# r8_3_1284.net
KiCad netlist of a schematic drawn in EAGLE
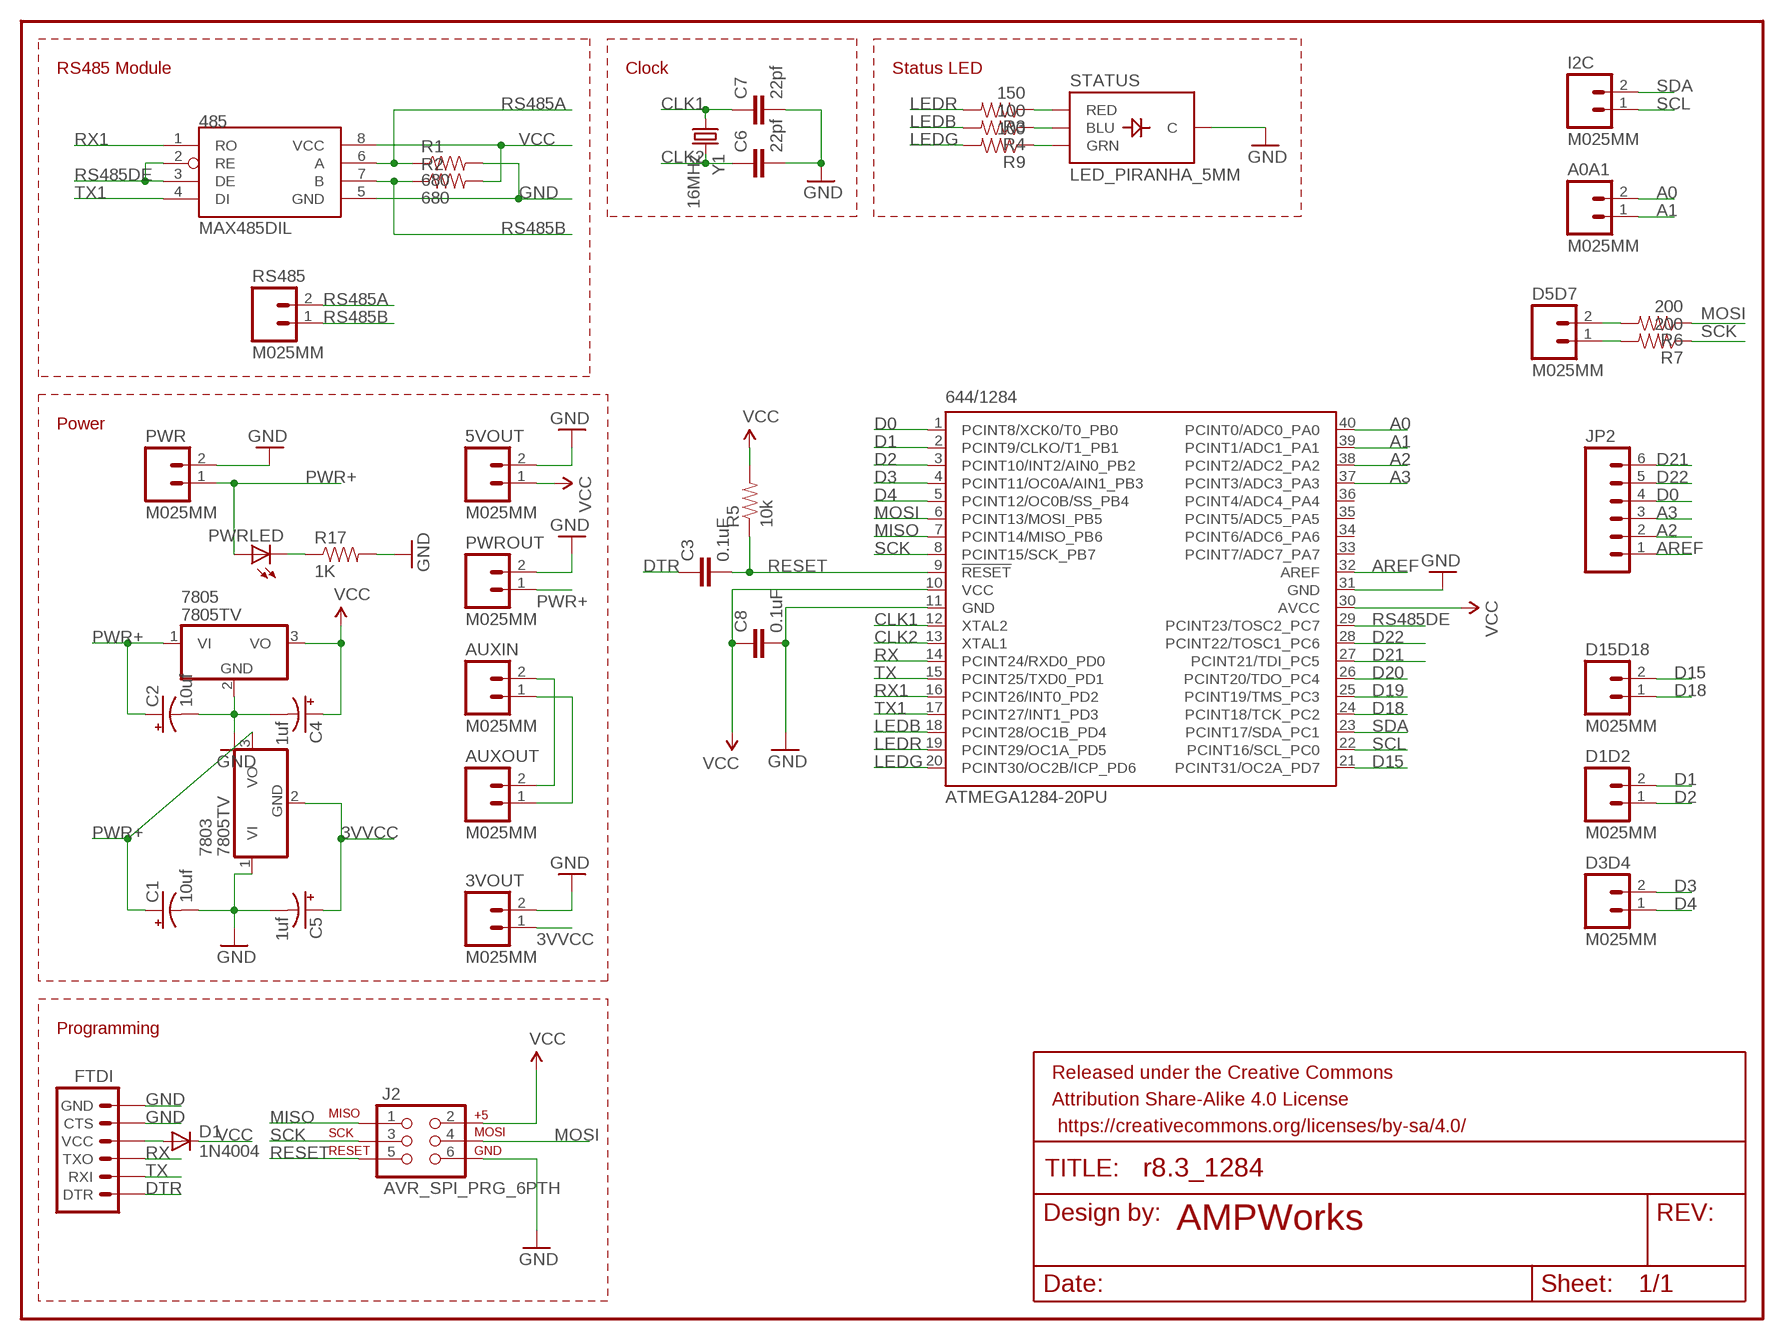
[diagram p0: schematic, sheet 1]

(export (version "E")
  (design (tool "Eeschema 10.0.6"))
  (components
    (comp (ref "3VOUT")
      (value "M025MM")
      (footprint "eagle-import:SCREWTERMINAL-5MM-2")
      (libsource (lib "eagle-import") (part "M025MM"))
    )
    (comp (ref "5VOUT")
      (value "M025MM")
      (footprint "eagle-import:SCREWTERMINAL-5MM-2")
      (libsource (lib "eagle-import") (part "M025MM"))
    )
    (comp (ref "485")
      (value "MAX485DIL")
      (footprint "eagle-import:DIL08")
      (libsource (lib "eagle-import") (part "MAX485DIL"))
    )
    (comp (ref "644/1284")
      (value "ATMEGA1284-20PU")
      (footprint "eagle-import:DIL40")
      (fields (field (name "MPN") "ATMEGA644-20PU"))
      (libsource (lib "eagle-import") (part "ATMEGA644-PU20"))
    )
    (comp (ref "7803")
      (value "7805TV")
      (footprint "eagle-import:TO220V")
      (libsource (lib "eagle-import") (part "78TV05"))
    )
    (comp (ref "7805")
      (value "7805TV")
      (footprint "eagle-import:TO220V")
      (libsource (lib "eagle-import") (part "78TV05"))
    )
    (comp (ref "A0A1")
      (value "M025MM")
      (footprint "eagle-import:SCREWTERMINAL-5MM-2")
      (libsource (lib "eagle-import") (part "M025MM"))
    )
    (comp (ref "AUXIN")
      (value "M025MM")
      (footprint "eagle-import:SCREWTERMINAL-5MM-2")
      (libsource (lib "eagle-import") (part "M025MM"))
    )
    (comp (ref "AUXOUT")
      (value "M025MM")
      (footprint "eagle-import:SCREWTERMINAL-5MM-2")
      (libsource (lib "eagle-import") (part "M025MM"))
    )
    (comp (ref "C1")
      (value "10uf")
      (footprint "eagle-import:CPOL-RADIAL-10UF-25V")
      (libsource (lib "eagle-import") (part "CAP_POLPTH2"))
    )
    (comp (ref "C2")
      (value "10uf")
      (footprint "eagle-import:CPOL-RADIAL-10UF-25V")
      (libsource (lib "eagle-import") (part "CAP_POLPTH2"))
    )
    (comp (ref "C3")
      (value "0.1uF")
      (footprint "eagle-import:CAP-PTH-SMALL")
      (libsource (lib "eagle-import") (part "CAPPTH"))
    )
    (comp (ref "C4")
      (value "1uf")
      (footprint "eagle-import:CPOL-RADIAL-10UF-25V")
      (libsource (lib "eagle-import") (part "CAP_POLPTH2"))
    )
    (comp (ref "C5")
      (value "1uf")
      (footprint "eagle-import:CPOL-RADIAL-10UF-25V")
      (libsource (lib "eagle-import") (part "CAP_POLPTH2"))
    )
    (comp (ref "C6")
      (value "22pf")
      (footprint "eagle-import:CAP-PTH-SMALL")
      (libsource (lib "eagle-import") (part "CAPPTH"))
    )
    (comp (ref "C7")
      (value "22pf")
      (footprint "eagle-import:CAP-PTH-SMALL")
      (libsource (lib "eagle-import") (part "CAPPTH"))
    )
    (comp (ref "C8")
      (value "0.1uF")
      (footprint "eagle-import:CAP-PTH-SMALL")
      (libsource (lib "eagle-import") (part "CAPPTH"))
    )
    (comp (ref "D1")
      (value "1N4004")
      (footprint "eagle-import:DO41-10")
      (libsource (lib "eagle-import") (part "1N4004"))
    )
    (comp (ref "D1D2")
      (value "M025MM")
      (footprint "eagle-import:SCREWTERMINAL-5MM-2")
      (libsource (lib "eagle-import") (part "M025MM"))
    )
    (comp (ref "D3D4")
      (value "M025MM")
      (footprint "eagle-import:SCREWTERMINAL-5MM-2")
      (libsource (lib "eagle-import") (part "M025MM"))
    )
    (comp (ref "D5D7")
      (value "M025MM")
      (footprint "eagle-import:SCREWTERMINAL-5MM-2")
      (libsource (lib "eagle-import") (part "M025MM"))
    )
    (comp (ref "D15D18")
      (value "M025MM")
      (footprint "eagle-import:SCREWTERMINAL-5MM-2")
      (libsource (lib "eagle-import") (part "M025MM"))
    )
    (comp (ref "FRAME1")
      (value "FRAME-LETTER")
      (footprint "eagle-import:CREATIVE_COMMONS")
      (libsource (lib "eagle-import") (part "FRAME-LETTER"))
    )
    (comp (ref "FTDI")
      (value "ARDUINO_SERIAL_PROGRAMPTH")
      (footprint "eagle-import:1X06")
      (libsource (lib "eagle-import") (part "ARDUINO_SERIAL_PROGRAMPTH"))
    )
    (comp (ref "I2C")
      (value "M025MM")
      (footprint "eagle-import:SCREWTERMINAL-5MM-2")
      (libsource (lib "eagle-import") (part "M025MM"))
    )
    (comp (ref "J2")
      (value "AVR_SPI_PRG_6PTH")
      (footprint "eagle-import:2X3")
      (libsource (lib "eagle-import") (part "AVR_SPI_PRG_6PTH"))
    )
    (comp (ref "JP2")
      (value "M06NO_SILK")
      (footprint "eagle-import:1X06_NO_SILK")
      (libsource (lib "eagle-import") (part "M06NO_SILK"))
    )
    (comp (ref "PWR")
      (value "M025MM")
      (footprint "eagle-import:SCREWTERMINAL-5MM-2")
      (libsource (lib "eagle-import") (part "M025MM"))
    )
    (comp (ref "PWRLED")
      (value "LED5MM")
      (footprint "eagle-import:LED5MM")
      (libsource (lib "eagle-import") (part "LED5MM"))
    )
    (comp (ref "PWROUT")
      (value "M025MM")
      (footprint "eagle-import:SCREWTERMINAL-5MM-2")
      (libsource (lib "eagle-import") (part "M025MM"))
    )
    (comp (ref "R1")
      (value "680")
      (footprint "eagle-import:AXIAL-0.4")
      (libsource (lib "eagle-import") (part "SparkFun-Resistors_RESISTORPTH-1/4W"))
    )
    (comp (ref "R2")
      (value "680")
      (footprint "eagle-import:AXIAL-0.4")
      (libsource (lib "eagle-import") (part "SparkFun-Resistors_RESISTORPTH-1/4W"))
    )
    (comp (ref "R3")
      (value "150")
      (footprint "eagle-import:AXIAL-0.4")
      (libsource (lib "eagle-import") (part "RESISTORPTH-1/4W"))
    )
    (comp (ref "R4")
      (value "100")
      (footprint "eagle-import:AXIAL-0.4")
      (libsource (lib "eagle-import") (part "RESISTORPTH-1/4W"))
    )
    (comp (ref "R5")
      (value "10k")
      (footprint "eagle-import:AXIAL-0.4")
      (libsource (lib "eagle-import") (part "RESISTORPTH-1/4W"))
    )
    (comp (ref "R6")
      (value "200")
      (footprint "eagle-import:AXIAL-0.4")
      (libsource (lib "eagle-import") (part "RESISTORPTH-1/4W"))
    )
    (comp (ref "R7")
      (value "200")
      (footprint "eagle-import:AXIAL-0.4")
      (libsource (lib "eagle-import") (part "RESISTORPTH-1/4W"))
    )
    (comp (ref "R9")
      (value "100")
      (footprint "eagle-import:AXIAL-0.4")
      (libsource (lib "eagle-import") (part "RESISTORPTH-1/4W"))
    )
    (comp (ref "R17")
      (value "1K")
      (footprint "eagle-import:AXIAL-0.4")
      (libsource (lib "eagle-import") (part "SparkFun-Resistors_RESISTORPTH-1/4W"))
    )
    (comp (ref "RS485")
      (value "M025MM")
      (footprint "eagle-import:SCREWTERMINAL-5MM-2")
      (libsource (lib "eagle-import") (part "M025MM"))
    )
    (comp (ref "STATUS")
      (value "LED_PIRANHA_5MM")
      (footprint "eagle-import:LED_PIRANHA_5MM")
      (libsource (lib "eagle-import") (part "LED_PIRANHA_5MM"))
    )
    (comp (ref "Y1")
      (value "16MHz")
      (footprint "eagle-import:HC49US")
      (libsource (lib "eagle-import") (part "CRYSTALHC49US"))
    )
  )
  (nets
    (net (code "1") (name "/3VVCC") (class "Default")
      (node (ref "3VOUT") (pin "1") (pinfunction "1_1") (pintype "passive"))
      (node (ref "7803") (pin "2") (pinfunction "GND_2") (pintype "passive"))
      (node (ref "C5") (pin "1") (pinfunction "+_1") (pintype "passive"))
    )
    (net (code "2") (name "/A0") (class "Default")
      (node (ref "644/1284") (pin "40") (pinfunction "PCINT0/ADC0_PA0_40") (pintype "bidirectional"))
      (node (ref "A0A1") (pin "2") (pinfunction "2_2") (pintype "passive"))
    )
    (net (code "3") (name "/A1") (class "Default")
      (node (ref "644/1284") (pin "39") (pinfunction "PCINT1/ADC1_PA1_39") (pintype "bidirectional"))
      (node (ref "A0A1") (pin "1") (pinfunction "1_1") (pintype "passive"))
    )
    (net (code "4") (name "/A2") (class "Default")
      (node (ref "644/1284") (pin "38") (pinfunction "PCINT2/ADC2_PA2_38") (pintype "bidirectional"))
      (node (ref "JP2") (pin "2") (pinfunction "2_2") (pintype "passive"))
    )
    (net (code "5") (name "/A3") (class "Default")
      (node (ref "644/1284") (pin "37") (pinfunction "PCINT3/ADC3_PA3_37") (pintype "bidirectional"))
      (node (ref "JP2") (pin "3") (pinfunction "3_3") (pintype "passive"))
    )
    (net (code "6") (name "/AREF") (class "Default")
      (node (ref "644/1284") (pin "32") (pinfunction "AREF_32") (pintype "passive"))
      (node (ref "JP2") (pin "1") (pinfunction "1_1") (pintype "passive"))
    )
    (net (code "7") (name "/CLK1") (class "Default")
      (node (ref "644/1284") (pin "12") (pinfunction "XTAL2_12") (pintype "output"))
      (node (ref "C7") (pin "1") (pinfunction "1_1") (pintype "passive"))
      (node (ref "Y1") (pin "1") (pinfunction "1_1") (pintype "passive"))
    )
    (net (code "8") (name "/CLK2") (class "Default")
      (node (ref "644/1284") (pin "13") (pinfunction "XTAL1_13") (pintype "input"))
      (node (ref "C6") (pin "1") (pinfunction "1_1") (pintype "passive"))
      (node (ref "Y1") (pin "2") (pinfunction "2_2") (pintype "passive"))
    )
    (net (code "9") (name "/D0") (class "Default")
      (node (ref "644/1284") (pin "1") (pinfunction "PCINT8/XCK0/T0_PB0_1") (pintype "bidirectional"))
      (node (ref "JP2") (pin "4") (pinfunction "4_4") (pintype "passive"))
    )
    (net (code "10") (name "/D1") (class "Default")
      (node (ref "644/1284") (pin "2") (pinfunction "PCINT9/CLKO/T1_PB1_2") (pintype "bidirectional"))
      (node (ref "D1D2") (pin "2") (pinfunction "2_2") (pintype "passive"))
    )
    (net (code "11") (name "/D2") (class "Default")
      (node (ref "644/1284") (pin "3") (pinfunction "PCINT10/INT2/AIN0_PB2_3") (pintype "bidirectional"))
      (node (ref "D1D2") (pin "1") (pinfunction "1_1") (pintype "passive"))
    )
    (net (code "12") (name "/D3") (class "Default")
      (node (ref "644/1284") (pin "4") (pinfunction "PCINT11/OC0A/AIN1_PB3_4") (pintype "bidirectional"))
      (node (ref "D3D4") (pin "2") (pinfunction "2_2") (pintype "passive"))
    )
    (net (code "13") (name "/D4") (class "Default")
      (node (ref "644/1284") (pin "5") (pinfunction "PCINT12/OC0B/SS_PB4_5") (pintype "bidirectional"))
      (node (ref "D3D4") (pin "1") (pinfunction "1_1") (pintype "passive"))
    )
    (net (code "14") (name "/D15") (class "Default")
      (node (ref "644/1284") (pin "21") (pinfunction "PCINT31/OC2A_PD7_21") (pintype "bidirectional"))
      (node (ref "D15D18") (pin "2") (pinfunction "2_2") (pintype "passive"))
    )
    (net (code "15") (name "/D18") (class "Default")
      (node (ref "644/1284") (pin "24") (pinfunction "PCINT18/TCK_PC2_24") (pintype "bidirectional"))
      (node (ref "D15D18") (pin "1") (pinfunction "1_1") (pintype "passive"))
    )
    (net (code "16") (name "/D19") (class "Default")
      (node (ref "644/1284") (pin "25") (pinfunction "PCINT19/TMS_PC3_25") (pintype "bidirectional"))
    )
    (net (code "17") (name "/D20") (class "Default")
      (node (ref "644/1284") (pin "26") (pinfunction "PCINT20/TDO_PC4_26") (pintype "bidirectional"))
    )
    (net (code "18") (name "/D21") (class "Default")
      (node (ref "644/1284") (pin "27") (pinfunction "PCINT21/TDI_PC5_27") (pintype "bidirectional"))
      (node (ref "JP2") (pin "6") (pinfunction "6_6") (pintype "passive"))
    )
    (net (code "19") (name "/D22") (class "Default")
      (node (ref "644/1284") (pin "28") (pinfunction "PCINT22/TOSC1_PC6_28") (pintype "bidirectional"))
      (node (ref "JP2") (pin "5") (pinfunction "5_5") (pintype "passive"))
    )
    (net (code "20") (name "/DTR") (class "Default")
      (node (ref "C3") (pin "1") (pinfunction "1_1") (pintype "passive"))
      (node (ref "FTDI") (pin "DTR") (pinfunction "DTR_DTR") (pintype "passive"))
    )
    (net (code "21") (name "/LEDB") (class "Default")
      (node (ref "644/1284") (pin "18") (pinfunction "PCINT28/OC1B_PD4_18") (pintype "bidirectional"))
      (node (ref "R4") (pin "P$2") (pinfunction "2_P$2") (pintype "passive"))
    )
    (net (code "22") (name "/LEDG") (class "Default")
      (node (ref "644/1284") (pin "20") (pinfunction "PCINT30/OC2B/ICP_PD6_20") (pintype "bidirectional"))
      (node (ref "R9") (pin "P$2") (pinfunction "2_P$2") (pintype "passive"))
    )
    (net (code "23") (name "/LEDR") (class "Default")
      (node (ref "644/1284") (pin "19") (pinfunction "PCINT29/OC1A_PD5_19") (pintype "bidirectional"))
      (node (ref "R3") (pin "P$2") (pinfunction "2_P$2") (pintype "passive"))
    )
    (net (code "24") (name "/MISO") (class "Default")
      (node (ref "644/1284") (pin "7") (pinfunction "PCINT14/MISO_PB6_7") (pintype "bidirectional"))
      (node (ref "J2") (pin "1") (pinfunction "1_1") (pintype "passive"))
    )
    (net (code "25") (name "/MOSI") (class "Default")
      (node (ref "644/1284") (pin "6") (pinfunction "PCINT13/MOSI_PB5_6") (pintype "bidirectional"))
      (node (ref "J2") (pin "4") (pinfunction "4_4") (pintype "passive"))
      (node (ref "R6") (pin "P$1") (pinfunction "1_P$1") (pintype "passive"))
    )
    (net (code "26") (name "/PWR+") (class "Default")
      (node (ref "7803") (pin "3") (pinfunction "VO_3") (pintype "passive"))
      (node (ref "7805") (pin "1") (pinfunction "VI_1") (pintype "input"))
      (node (ref "C1") (pin "1") (pinfunction "+_1") (pintype "passive"))
      (node (ref "C2") (pin "1") (pinfunction "+_1") (pintype "passive"))
      (node (ref "PWR") (pin "1") (pinfunction "1_1") (pintype "passive"))
      (node (ref "PWRLED") (pin "A") (pinfunction "A_A") (pintype "passive"))
      (node (ref "PWROUT") (pin "1") (pinfunction "1_1") (pintype "passive"))
    )
    (net (code "27") (name "/RESET") (class "Default")
      (node (ref "644/1284") (pin "9") (pinfunction "~{RESET}_9") (pintype "input"))
      (node (ref "C3") (pin "2") (pinfunction "2_2") (pintype "passive"))
      (node (ref "J2") (pin "5") (pinfunction "5_5") (pintype "passive"))
      (node (ref "R5") (pin "P$1") (pinfunction "1_P$1") (pintype "passive"))
    )
    (net (code "28") (name "/RS485A") (class "Default")
      (node (ref "485") (pin "6") (pinfunction "A_6") (pintype "bidirectional"))
      (node (ref "R1") (pin "P$1") (pinfunction "1_P$1") (pintype "passive"))
      (node (ref "RS485") (pin "2") (pinfunction "2_2") (pintype "passive"))
    )
    (net (code "29") (name "/RS485B") (class "Default")
      (node (ref "485") (pin "7") (pinfunction "B_7") (pintype "bidirectional"))
      (node (ref "R2") (pin "P$1") (pinfunction "1_P$1") (pintype "passive"))
      (node (ref "RS485") (pin "1") (pinfunction "1_1") (pintype "passive"))
    )
    (net (code "30") (name "/RS485DE") (class "Default")
      (node (ref "485") (pin "2") (pinfunction "RE_2") (pintype "bidirectional"))
      (node (ref "485") (pin "3") (pinfunction "DE_3") (pintype "bidirectional"))
      (node (ref "644/1284") (pin "29") (pinfunction "PCINT23/TOSC2_PC7_29") (pintype "bidirectional"))
    )
    (net (code "31") (name "/RX") (class "Default")
      (node (ref "644/1284") (pin "14") (pinfunction "PCINT24/RXD0_PD0_14") (pintype "bidirectional"))
      (node (ref "FTDI") (pin "TXO") (pinfunction "TXO_TXO") (pintype "passive"))
    )
    (net (code "32") (name "/RX1") (class "Default")
      (node (ref "485") (pin "1") (pinfunction "RO_1") (pintype "bidirectional"))
      (node (ref "644/1284") (pin "16") (pinfunction "PCINT26/INT0_PD2_16") (pintype "bidirectional"))
    )
    (net (code "33") (name "/SCK") (class "Default")
      (node (ref "644/1284") (pin "8") (pinfunction "PCINT15/SCK_PB7_8") (pintype "bidirectional"))
      (node (ref "J2") (pin "3") (pinfunction "3_3") (pintype "passive"))
      (node (ref "R7") (pin "P$1") (pinfunction "1_P$1") (pintype "passive"))
    )
    (net (code "34") (name "/SCL") (class "Default")
      (node (ref "644/1284") (pin "22") (pinfunction "PCINT16/SCL_PC0_22") (pintype "bidirectional"))
      (node (ref "I2C") (pin "1") (pinfunction "1_1") (pintype "passive"))
    )
    (net (code "35") (name "/SDA") (class "Default")
      (node (ref "644/1284") (pin "23") (pinfunction "PCINT17/SDA_PC1_23") (pintype "bidirectional"))
      (node (ref "I2C") (pin "2") (pinfunction "2_2") (pintype "passive"))
    )
    (net (code "36") (name "/TX") (class "Default")
      (node (ref "644/1284") (pin "15") (pinfunction "PCINT25/TXD0_PD1_15") (pintype "bidirectional"))
      (node (ref "FTDI") (pin "RXI") (pinfunction "RXI_RXI") (pintype "passive"))
    )
    (net (code "37") (name "/TX1") (class "Default")
      (node (ref "485") (pin "4") (pinfunction "DI_4") (pintype "bidirectional"))
      (node (ref "644/1284") (pin "17") (pinfunction "PCINT27/INT1_PD3_17") (pintype "bidirectional"))
    )
    (net (code "38") (name "GND") (class "Default")
      (node (ref "3VOUT") (pin "2") (pinfunction "2_2") (pintype "passive"))
      (node (ref "485") (pin "5") (pinfunction "GND_5") (pintype "bidirectional"))
      (node (ref "5VOUT") (pin "2") (pinfunction "2_2") (pintype "passive"))
      (node (ref "644/1284") (pin "11") (pinfunction "GND_11") (pintype "power_in"))
      (node (ref "644/1284") (pin "31") (pinfunction "GND_31") (pintype "power_in"))
      (node (ref "7803") (pin "1") (pinfunction "VI_1") (pintype "input"))
      (node (ref "7805") (pin "2") (pinfunction "GND_2") (pintype "passive"))
      (node (ref "C1") (pin "2") (pinfunction "-_2") (pintype "passive"))
      (node (ref "C2") (pin "2") (pinfunction "-_2") (pintype "passive"))
      (node (ref "C4") (pin "2") (pinfunction "-_2") (pintype "passive"))
      (node (ref "C5") (pin "2") (pinfunction "-_2") (pintype "passive"))
      (node (ref "C6") (pin "2") (pinfunction "2_2") (pintype "passive"))
      (node (ref "C7") (pin "2") (pinfunction "2_2") (pintype "passive"))
      (node (ref "C8") (pin "2") (pinfunction "2_2") (pintype "passive"))
      (node (ref "FTDI") (pin "CTS") (pinfunction "CTS_CTS") (pintype "passive"))
      (node (ref "FTDI") (pin "GND") (pinfunction "GND_GND") (pintype "passive"))
      (node (ref "J2") (pin "6") (pinfunction "6_6") (pintype "passive"))
      (node (ref "PWR") (pin "2") (pinfunction "2_2") (pintype "passive"))
      (node (ref "PWROUT") (pin "2") (pinfunction "2_2") (pintype "passive"))
      (node (ref "R1") (pin "P$2") (pinfunction "2_P$2") (pintype "passive"))
      (node (ref "R17") (pin "P$2") (pinfunction "2_P$2") (pintype "passive"))
      (node (ref "STATUS") (pin "-") (pinfunction "C_-") (pintype "bidirectional"))
    )
    (net (code "39") (name "Net-(AUXIN-Pad1)") (class "Default")
      (node (ref "AUXIN") (pin "1") (pinfunction "1_1") (pintype "passive"))
      (node (ref "AUXOUT") (pin "1") (pinfunction "1_1") (pintype "passive"))
    )
    (net (code "40") (name "Net-(AUXIN-Pad2)") (class "Default")
      (node (ref "AUXIN") (pin "2") (pinfunction "2_2") (pintype "passive"))
      (node (ref "AUXOUT") (pin "2") (pinfunction "2_2") (pintype "passive"))
    )
    (net (code "41") (name "Net-(D1-PadA)") (class "Default")
      (node (ref "D1") (pin "A") (pinfunction "A_A") (pintype "passive"))
      (node (ref "FTDI") (pin "VCC") (pinfunction "VCC_VCC") (pintype "passive"))
    )
    (net (code "42") (name "Net-(PWRLED-C)") (class "Default")
      (node (ref "PWRLED") (pin "K") (pinfunction "C_K") (pintype "passive"))
      (node (ref "R17") (pin "P$1") (pinfunction "1_P$1") (pintype "passive"))
    )
    (net (code "43") (name "Net-(R3-1)") (class "Default")
      (node (ref "R3") (pin "P$1") (pinfunction "1_P$1") (pintype "passive"))
      (node (ref "STATUS") (pin "R") (pinfunction "RED_R") (pintype "bidirectional"))
    )
    (net (code "44") (name "Net-(R4-1)") (class "Default")
      (node (ref "R4") (pin "P$1") (pinfunction "1_P$1") (pintype "passive"))
      (node (ref "STATUS") (pin "B") (pinfunction "BLU_B") (pintype "bidirectional"))
    )
    (net (code "45") (name "Net-(R6-2)") (class "Default")
      (node (ref "D5D7") (pin "2") (pinfunction "2_2") (pintype "passive"))
      (node (ref "R6") (pin "P$2") (pinfunction "2_P$2") (pintype "passive"))
    )
    (net (code "46") (name "Net-(R7-2)") (class "Default")
      (node (ref "D5D7") (pin "1") (pinfunction "1_1") (pintype "passive"))
      (node (ref "R7") (pin "P$2") (pinfunction "2_P$2") (pintype "passive"))
    )
    (net (code "47") (name "Net-(R9-1)") (class "Default")
      (node (ref "R9") (pin "P$1") (pinfunction "1_P$1") (pintype "passive"))
      (node (ref "STATUS") (pin "G") (pinfunction "GRN_G") (pintype "bidirectional"))
    )
    (net (code "48") (name "VCC") (class "Default")
      (node (ref "485") (pin "8") (pinfunction "VCC_8") (pintype "bidirectional"))
      (node (ref "5VOUT") (pin "1") (pinfunction "1_1") (pintype "passive"))
      (node (ref "644/1284") (pin "10") (pinfunction "VCC_10") (pintype "power_in"))
      (node (ref "644/1284") (pin "30") (pinfunction "AVCC_30") (pintype "power_in"))
      (node (ref "7805") (pin "3") (pinfunction "VO_3") (pintype "passive"))
      (node (ref "C4") (pin "1") (pinfunction "+_1") (pintype "passive"))
      (node (ref "C8") (pin "1") (pinfunction "1_1") (pintype "passive"))
      (node (ref "D1") (pin "C") (pinfunction "C_C") (pintype "passive"))
      (node (ref "J2") (pin "2") (pinfunction "2_2") (pintype "passive"))
      (node (ref "R2") (pin "P$2") (pinfunction "2_P$2") (pintype "passive"))
      (node (ref "R5") (pin "P$2") (pinfunction "2_P$2") (pintype "passive"))
    )
    (net (code "49") (name "unconnected-(644/1284-PCINT4{slash}ADC4_PA4-Pad36)") (class "Default")
      (node (ref "644/1284") (pin "36") (pinfunction "PCINT4/ADC4_PA4_36") (pintype "bidirectional"))
    )
    (net (code "50") (name "unconnected-(644/1284-PCINT5{slash}ADC5_PA5-Pad35)") (class "Default")
      (node (ref "644/1284") (pin "35") (pinfunction "PCINT5/ADC5_PA5_35") (pintype "bidirectional"))
    )
    (net (code "51") (name "unconnected-(644/1284-PCINT6{slash}ADC6_PA6-Pad34)") (class "Default")
      (node (ref "644/1284") (pin "34") (pinfunction "PCINT6/ADC6_PA6_34") (pintype "bidirectional"))
    )
    (net (code "52") (name "unconnected-(644/1284-PCINT7{slash}ADC7_PA7-Pad33)") (class "Default")
      (node (ref "644/1284") (pin "33") (pinfunction "PCINT7/ADC7_PA7_33") (pintype "bidirectional"))
    )
  )
)
